# Power_Supply.net
KiCad netlist of a schematic drawn in Altium Designer
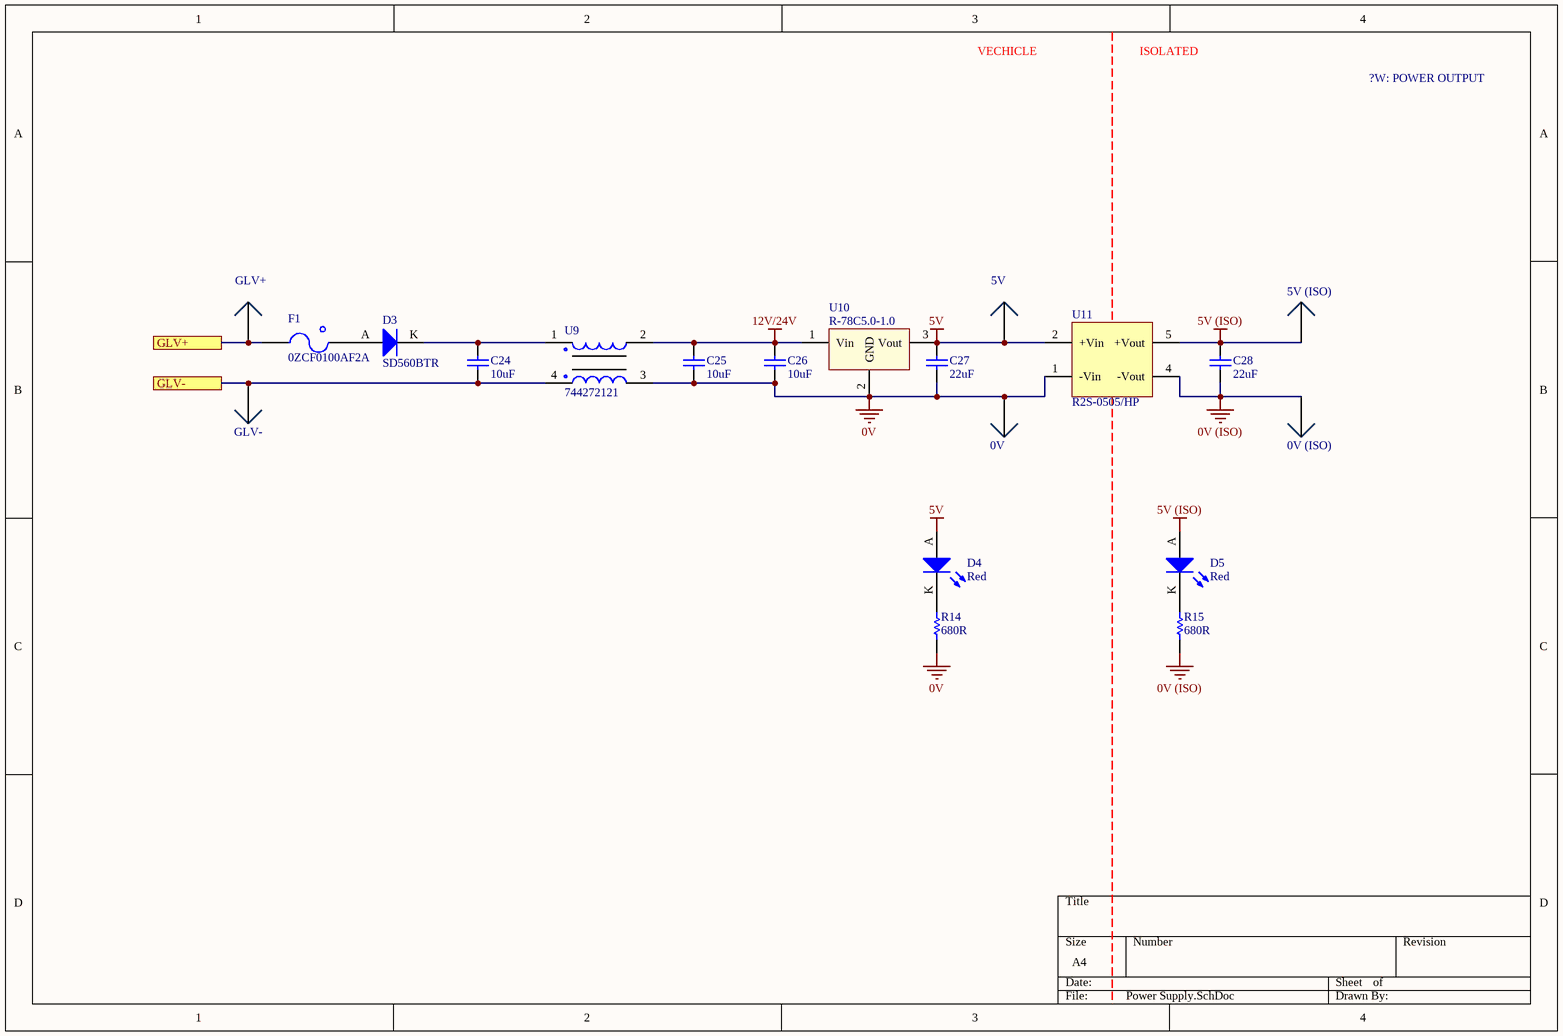
[diagram p0: Power Supply.SchDoc]

(export (version "E")
  (design (tool "Eeschema 10.0.6"))
  (components
    (comp (ref "0V")
      (value "0mm")
      (footprint "SMD Test Point")
      (fields (field (name "PART NUMBER") "SMD Test Point") (field (name "CONTACT") "NA"))
      (libsource (lib "ts_20-standard-connectors") (part "Test Point"))
    )
    (comp (ref "0V (ISO)")
      (value "0mm")
      (footprint "SMD Test Point")
      (fields (field (name "PART NUMBER") "SMD Test Point") (field (name "CONTACT") "NA"))
      (libsource (lib "ts_20-standard-connectors") (part "Test Point"))
    )
    (comp (ref "5V")
      (value "0mm")
      (footprint "SMD Test Point")
      (fields (field (name "PART NUMBER") "SMD Test Point") (field (name "CONTACT") "NA"))
      (libsource (lib "ts_20-standard-connectors") (part "Test Point"))
    )
    (comp (ref "5V (ISO)")
      (value "0mm")
      (footprint "SMD Test Point")
      (fields (field (name "PART NUMBER") "SMD Test Point") (field (name "CONTACT") "NA"))
      (libsource (lib "ts_20-standard-connectors") (part "Test Point"))
    )
    (comp (ref "C24")
      (value "10uF")
      (footprint "0805")
      (fields
        (field (name "PART NUMBER") "GRM21BR6YA106KE43L")
        (field (name "TOLERANCE") "10%")
        (field (name "MANUFACTURER") "muRata")
      )
      (libsource (lib "ts_20-standard-library") (part "Capacitor"))
    )
    (comp (ref "C25")
      (value "10uF")
      (footprint "0805")
      (fields
        (field (name "PART NUMBER") "GRM21BR6YA106KE43L")
        (field (name "TOLERANCE") "10%")
        (field (name "MANUFACTURER") "muRata")
      )
      (libsource (lib "ts_20-standard-library") (part "Capacitor"))
    )
    (comp (ref "C26")
      (value "10uF")
      (footprint "0805")
      (fields
        (field (name "PART NUMBER") "GRM21BR6YA106KE43L")
        (field (name "TOLERANCE") "10%")
        (field (name "MANUFACTURER") "muRata")
      )
      (libsource (lib "ts_20-standard-library") (part "Capacitor"))
    )
    (comp (ref "C27")
      (value "22uF")
      (footprint "1206")
      (fields
        (field (name "PART NUMBER") "CC1206MKX5R7BB226")
        (field (name "TOLERANCE") "20%")
        (field (name "MANUFACTURER") "YAGEO")
      )
      (libsource (lib "ts_20-standard-library") (part "Capacitor"))
    )
    (comp (ref "C28")
      (value "22uF")
      (footprint "1206")
      (fields
        (field (name "PART NUMBER") "CC1206MKX5R7BB226")
        (field (name "TOLERANCE") "20%")
        (field (name "MANUFACTURER") "YAGEO")
      )
      (libsource (lib "ts_20-standard-library") (part "Capacitor"))
    )
    (comp (ref "D3")
      (value "SD560BTR")
      (footprint "SMB Diode")
      (description "1.2V_F 600V 5A SMB")
      (fields
        (field (name "MANUFACTURER") "SMC Diode Solutions")
        (field (name "DIGIKEY PART NUMBER") "1655-1530-2-ND")
      )
      (libsource (lib "ts_20-standard-library") (part "Diode"))
    )
    (comp (ref "D4")
      (value "Red")
      (footprint "0805 LED")
      (description "Red LED Indication - Discrete 1.75V 0805 (2012 Metric)")
      (fields (field (name "PART NUMBER") "SML-210LTT86") (field (name "MANUFACTURER") "ROHM Semiconductor"))
      (libsource (lib "ts_20-standard-library") (part "LED"))
    )
    (comp (ref "D5")
      (value "Red")
      (footprint "0805 LED")
      (description "Red LED Indication - Discrete 1.75V 0805 (2012 Metric)")
      (fields (field (name "PART NUMBER") "SML-210LTT86") (field (name "MANUFACTURER") "ROHM Semiconductor"))
      (libsource (lib "ts_20-standard-library") (part "LED"))
    )
    (comp (ref "F1")
      (value "0ZCF0100AF2A")
      (footprint "2920")
      (description "PTC RESET FUSE 60V 1A 292")
      (fields
        (field (name "MANUFACTURER") "Littelfuse Inc.")
        (field (name "DIGIKEY PART NUMBER") "507-2070-1-ND")
      )
      (libsource (lib "ts_20-standard-library") (part "PTC Fuse"))
    )
    (comp (ref "GLV+")
      (value "0mm")
      (footprint "SMD Test Point")
      (fields (field (name "PART NUMBER") "SMD Test Point") (field (name "CONTACT") "NA"))
      (libsource (lib "ts_20-standard-connectors") (part "Test Point"))
    )
    (comp (ref "GLV-")
      (value "0mm")
      (footprint "SMD Test Point")
      (fields (field (name "PART NUMBER") "SMD Test Point") (field (name "CONTACT") "NA"))
      (libsource (lib "ts_20-standard-connectors") (part "Test Point"))
    )
    (comp (ref "R14")
      (value "680R")
      (footprint "0805")
      (fields
        (field (name "PART NUMBER") "RC0805FR07680RL")
        (field (name "MANUFACTURER") "YAGEO")
        (field (name "TOLERANCE") "0.01")
      )
      (libsource (lib "ts_20-standard-library") (part "Resistor"))
    )
    (comp (ref "R15")
      (value "680R")
      (footprint "0805")
      (fields
        (field (name "PART NUMBER") "RC0805FR07680RL")
        (field (name "MANUFACTURER") "YAGEO")
        (field (name "TOLERANCE") "0.01")
      )
      (libsource (lib "ts_20-standard-library") (part "Resistor"))
    )
    (comp (ref "U9")
      (value "744272121")
      (footprint "Wurth 4-PC Pad")
      (description "120µH @ 100kHz 2 Line Common Mode Choke Surface Mount 460 Ohms @ 30MHz 2.5A DCR 25mOhm")
      (fields
        (field (name "MANUFACTURER") "Wurth Electronics Inc")
        (field (name "DIGIKEY PART NUMBER") "732-1489-1-ND")
      )
      (libsource (lib "ts_20-standard-library") (part "744272121"))
    )
    (comp (ref "U10")
      (value "R-78C5.0-1.0")
      (footprint "RECOM 3-SIP")
      (description "CONV DC/DC 1A 5V OUT SIP VERT")
      (fields (field (name "MANUFACTURER") "Recom") (field (name "DIGIKEY PART NUMBER") "945-1395-5-ND"))
      (libsource (lib "ts_20-standard-library") (part "R-78C5.0-1.0"))
    )
    (comp (ref "U11")
      (value "R2S-0505/HP")
      (footprint "RECOM 8-SMD (5 Pin)")
      (description "Isolated Module DC DC Converter 1 Output 3.3V 606mA 4.5V - 5.5V Input")
      (fields (field (name "MANUFACTURER") "Recom") (field (name "DIGIKEY PART NUMBER") "945-1764-5-ND"))
      (libsource (lib "ts_20-standard-library") (part "R2S-0505/HP"))
    )
  )
  (nets
    (net (code "1") (name "/GLV+") (class "Default")
      (node (ref "F1") (pin "1") (pinfunction "1_1") (pintype "passive"))
      (node (ref "GLV+") (pin "1") (pinfunction "1_1") (pintype "passive"))
    )
    (net (code "2") (name "/GLV-") (class "Default")
      (node (ref "C24") (pin "1") (pinfunction "1_1") (pintype "passive"))
      (node (ref "GLV-") (pin "1") (pinfunction "1_1") (pintype "passive"))
      (node (ref "U9") (pin "4") (pinfunction "4_4") (pintype "passive"))
    )
    (net (code "3") (name "0V") (class "Default")
      (node (ref "0V") (pin "1") (pinfunction "1_1") (pintype "passive"))
      (node (ref "C25") (pin "1") (pinfunction "1_1") (pintype "passive"))
      (node (ref "C26") (pin "1") (pinfunction "1_1") (pintype "passive"))
      (node (ref "C27") (pin "1") (pinfunction "1_1") (pintype "passive"))
      (node (ref "R14") (pin "1") (pinfunction "1_1") (pintype "passive"))
      (node (ref "U10") (pin "2") (pinfunction "GND_2") (pintype "passive"))
      (node (ref "U11") (pin "1") (pinfunction "-Vin_1") (pintype "power_in"))
      (node (ref "U9") (pin "3") (pinfunction "3_3") (pintype "power_in"))
    )
    (net (code "4") (name "0V (ISO)") (class "Default")
      (node (ref "0V (ISO)") (pin "1") (pinfunction "1_1") (pintype "passive"))
      (node (ref "C28") (pin "1") (pinfunction "1_1") (pintype "passive"))
      (node (ref "R15") (pin "1") (pinfunction "1_1") (pintype "passive"))
      (node (ref "U11") (pin "4") (pinfunction "-Vout_4") (pintype "power_in"))
    )
    (net (code "5") (name "5V") (class "Default")
      (node (ref "5V") (pin "1") (pinfunction "1_1") (pintype "passive"))
      (node (ref "C27") (pin "2") (pinfunction "2_2") (pintype "passive"))
      (node (ref "D4") (pin "A") (pinfunction "A_A") (pintype "passive"))
      (node (ref "U10") (pin "3") (pinfunction "Vout_3") (pintype "passive"))
      (node (ref "U11") (pin "2") (pinfunction "+Vin_2") (pintype "power_in"))
    )
    (net (code "6") (name "5V (ISO)") (class "Default")
      (node (ref "5V (ISO)") (pin "1") (pinfunction "1_1") (pintype "passive"))
      (node (ref "C28") (pin "2") (pinfunction "2_2") (pintype "passive"))
      (node (ref "D5") (pin "A") (pinfunction "A_A") (pintype "passive"))
      (node (ref "U11") (pin "5") (pinfunction "+Vout_5") (pintype "power_in"))
    )
    (net (code "7") (name "12V{slash}24V") (class "Default")
      (node (ref "C25") (pin "2") (pinfunction "2_2") (pintype "passive"))
      (node (ref "C26") (pin "2") (pinfunction "2_2") (pintype "passive"))
      (node (ref "U10") (pin "1") (pinfunction "Vin_1") (pintype "passive"))
      (node (ref "U9") (pin "2") (pinfunction "2_2") (pintype "passive"))
    )
    (net (code "8") (name "Net-(C24-Pad2)") (class "Default")
      (node (ref "C24") (pin "2") (pinfunction "2_2") (pintype "passive"))
      (node (ref "D3") (pin "K") (pinfunction "K_K") (pintype "passive"))
      (node (ref "U9") (pin "1") (pinfunction "1_1") (pintype "passive"))
    )
    (net (code "9") (name "Net-(D3-PadA)") (class "Default")
      (node (ref "D3") (pin "A") (pinfunction "A_A") (pintype "passive"))
      (node (ref "F1") (pin "2") (pinfunction "2_2") (pintype "passive"))
    )
    (net (code "10") (name "Net-(D4-PadK)") (class "Default")
      (node (ref "D4") (pin "K") (pinfunction "K_K") (pintype "passive"))
      (node (ref "R14") (pin "2") (pinfunction "2_2") (pintype "passive"))
    )
    (net (code "11") (name "Net-(D5-PadK)") (class "Default")
      (node (ref "D5") (pin "K") (pinfunction "K_K") (pintype "passive"))
      (node (ref "R15") (pin "2") (pinfunction "2_2") (pintype "passive"))
    )
  )
)
